# GPS_MPU_Schematic.net
KiCad netlist of a schematic drawn in EasyEDA
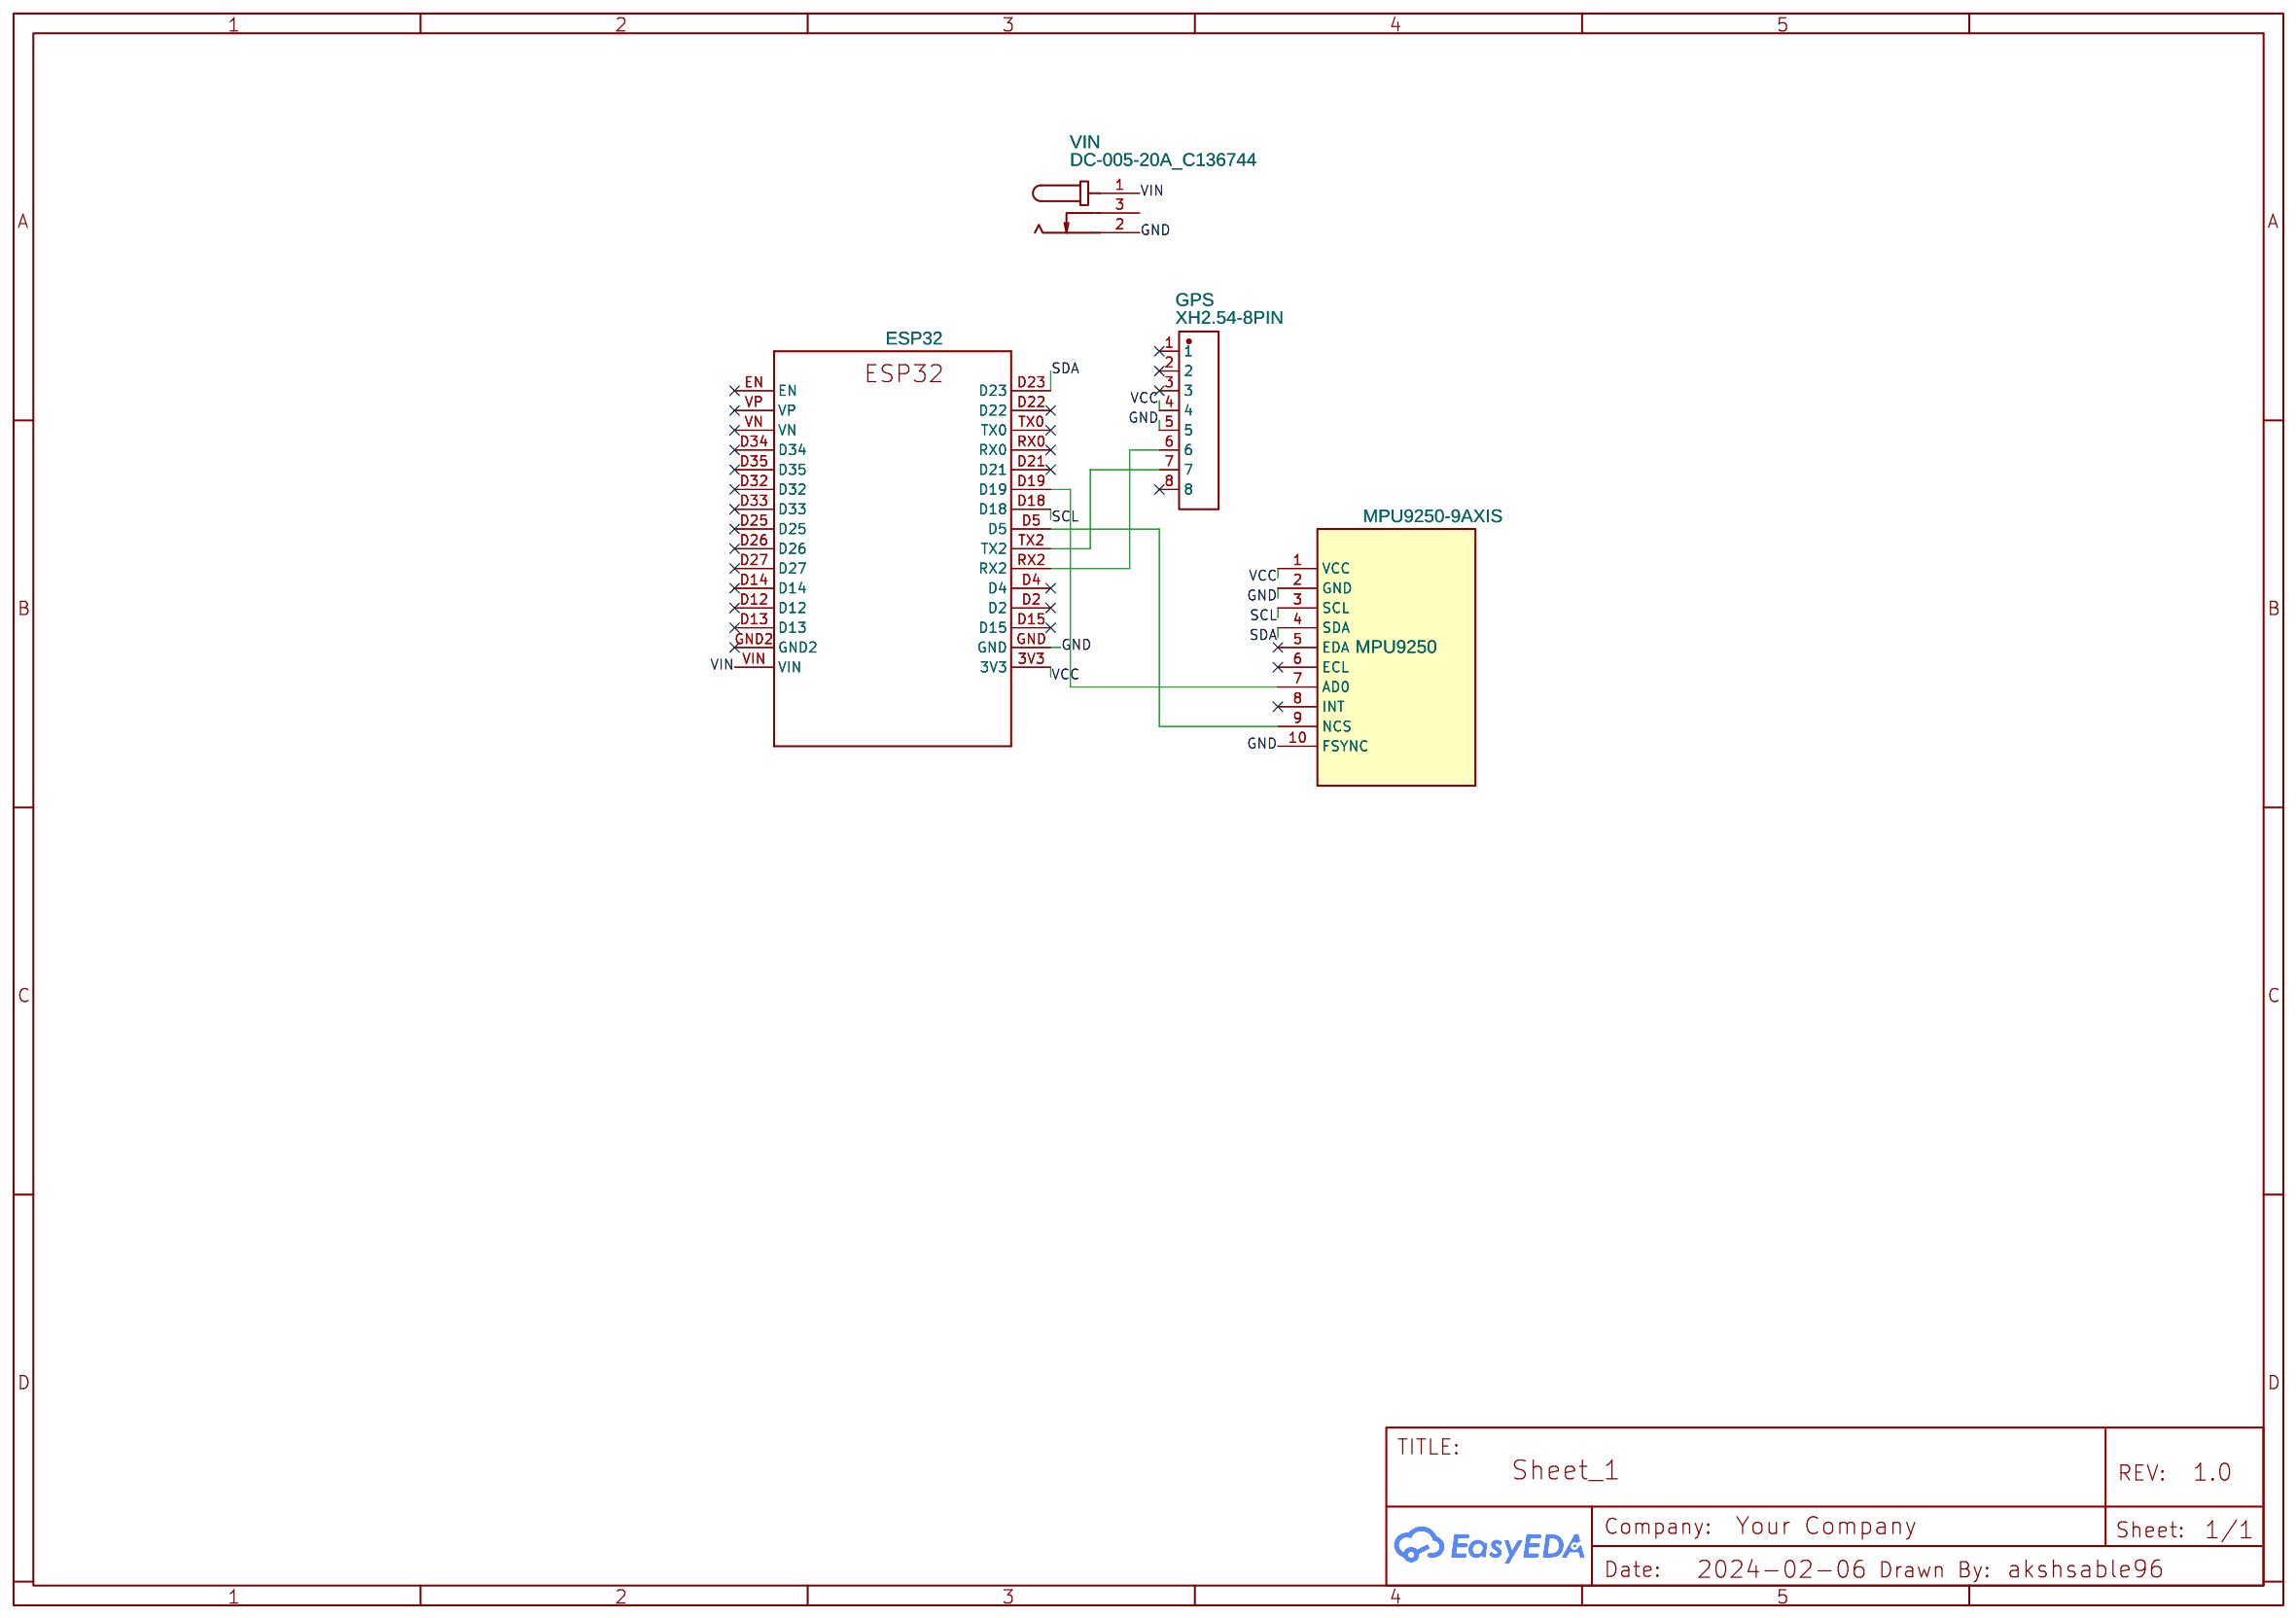
[diagram p0: schematic sheet]

(export (version "E")
  (design (tool "Eeschema 10.0.6"))
  (components
    (comp (ref "2") (value "ESP32") (libsource (lib "") (part "ESP32-DEVKIT-V1-30PIN")))
    (comp (ref "GPS") (value "XH2.54-8PIN") (libsource (lib "") (part "XH2.54-8PIN")))
    (comp (ref "MPU9250") (value "MPU9250-9AXIS") (libsource (lib "") (part "MPU9250-9AXIS")))
    (comp (ref "VIN")
      (value "DC-005-20A_C136744")
      (fields (field (name "Manufacturer Part") "DC-005-20A") (field (name "Manufacturer") "韩国韩荣"))
      (libsource (lib "") (part "DC-005-20A_C136744"))
    )
  )
  (nets
    (net (code "1") (name "/GND") (class "Default")
      (node (ref "2") (pin "GND") (pinfunction "GND_GND") (pintype "unspecified"))
      (node (ref "GPS") (pin "5") (pinfunction "5_5") (pintype "unspecified"))
      (node (ref "MPU9250") (pin "10") (pinfunction "FSYNC_10") (pintype "unspecified"))
      (node (ref "MPU9250") (pin "2") (pinfunction "GND_2") (pintype "unspecified"))
      (node (ref "VIN") (pin "2") (pinfunction "2_2") (pintype "unspecified"))
    )
    (net (code "2") (name "/SCL") (class "Default")
      (node (ref "2") (pin "D18") (pinfunction "D18_D18") (pintype "unspecified"))
      (node (ref "MPU9250") (pin "3") (pinfunction "SCL_3") (pintype "unspecified"))
    )
    (net (code "3") (name "/SDA") (class "Default")
      (node (ref "2") (pin "D23") (pinfunction "D23_D23") (pintype "unspecified"))
      (node (ref "MPU9250") (pin "4") (pinfunction "SDA_4") (pintype "unspecified"))
    )
    (net (code "4") (name "/VCC") (class "Default")
      (node (ref "2") (pin "3V3") (pinfunction "3V3_3V3") (pintype "unspecified"))
      (node (ref "GPS") (pin "4") (pinfunction "4_4") (pintype "unspecified"))
      (node (ref "MPU9250") (pin "1") (pinfunction "VCC_1") (pintype "unspecified"))
    )
    (net (code "5") (name "/VIN") (class "Default")
      (node (ref "2") (pin "VIN") (pinfunction "VIN_VIN") (pintype "unspecified"))
      (node (ref "VIN") (pin "1") (pinfunction "1_1") (pintype "unspecified"))
    )
    (net (code "6") (name "Net-(2-PadRX2)") (class "Default")
      (node (ref "2") (pin "RX2") (pinfunction "RX2_RX2") (pintype "unspecified"))
      (node (ref "GPS") (pin "6") (pinfunction "6_6") (pintype "unspecified"))
    )
    (net (code "7") (name "Net-(2-PadTX2)") (class "Default")
      (node (ref "2") (pin "TX2") (pinfunction "TX2_TX2") (pintype "unspecified"))
      (node (ref "GPS") (pin "7") (pinfunction "7_7") (pintype "unspecified"))
    )
    (net (code "8") (name "Net-(MPU9250-AD0)") (class "Default")
      (node (ref "2") (pin "D19") (pinfunction "D19_D19") (pintype "unspecified"))
      (node (ref "MPU9250") (pin "7") (pinfunction "AD0_7") (pintype "unspecified"))
    )
    (net (code "9") (name "Net-(MPU9250-NCS)") (class "Default")
      (node (ref "2") (pin "D5") (pinfunction "D5_D5") (pintype "unspecified"))
      (node (ref "MPU9250") (pin "9") (pinfunction "NCS_9") (pintype "unspecified"))
    )
    (net (code "10") (name "unconnected-(2-PadD2)") (class "Default")
      (node (ref "2") (pin "D2") (pinfunction "D2_D2") (pintype "unspecified+no_connect"))
    )
    (net (code "11") (name "unconnected-(2-PadD4)") (class "Default")
      (node (ref "2") (pin "D4") (pinfunction "D4_D4") (pintype "unspecified+no_connect"))
    )
    (net (code "12") (name "unconnected-(2-PadD12)") (class "Default")
      (node (ref "2") (pin "D12") (pinfunction "D12_D12") (pintype "unspecified+no_connect"))
    )
    (net (code "13") (name "unconnected-(2-PadD13)") (class "Default")
      (node (ref "2") (pin "D13") (pinfunction "D13_D13") (pintype "unspecified+no_connect"))
    )
    (net (code "14") (name "unconnected-(2-PadD14)") (class "Default")
      (node (ref "2") (pin "D14") (pinfunction "D14_D14") (pintype "unspecified+no_connect"))
    )
    (net (code "15") (name "unconnected-(2-PadD15)") (class "Default")
      (node (ref "2") (pin "D15") (pinfunction "D15_D15") (pintype "unspecified+no_connect"))
    )
    (net (code "16") (name "unconnected-(2-PadD21)") (class "Default")
      (node (ref "2") (pin "D21") (pinfunction "D21_D21") (pintype "unspecified+no_connect"))
    )
    (net (code "17") (name "unconnected-(2-PadD22)") (class "Default")
      (node (ref "2") (pin "D22") (pinfunction "D22_D22") (pintype "unspecified+no_connect"))
    )
    (net (code "18") (name "unconnected-(2-PadD25)") (class "Default")
      (node (ref "2") (pin "D25") (pinfunction "D25_D25") (pintype "unspecified+no_connect"))
    )
    (net (code "19") (name "unconnected-(2-PadD26)") (class "Default")
      (node (ref "2") (pin "D26") (pinfunction "D26_D26") (pintype "unspecified+no_connect"))
    )
    (net (code "20") (name "unconnected-(2-PadD27)") (class "Default")
      (node (ref "2") (pin "D27") (pinfunction "D27_D27") (pintype "unspecified+no_connect"))
    )
    (net (code "21") (name "unconnected-(2-PadD32)") (class "Default")
      (node (ref "2") (pin "D32") (pinfunction "D32_D32") (pintype "unspecified+no_connect"))
    )
    (net (code "22") (name "unconnected-(2-PadD33)") (class "Default")
      (node (ref "2") (pin "D33") (pinfunction "D33_D33") (pintype "unspecified+no_connect"))
    )
    (net (code "23") (name "unconnected-(2-PadD34)") (class "Default")
      (node (ref "2") (pin "D34") (pinfunction "D34_D34") (pintype "unspecified+no_connect"))
    )
    (net (code "24") (name "unconnected-(2-PadD35)") (class "Default")
      (node (ref "2") (pin "D35") (pinfunction "D35_D35") (pintype "unspecified+no_connect"))
    )
    (net (code "25") (name "unconnected-(2-PadEN)") (class "Default")
      (node (ref "2") (pin "EN") (pinfunction "EN_EN") (pintype "unspecified+no_connect"))
    )
    (net (code "26") (name "unconnected-(2-PadGND2)") (class "Default")
      (node (ref "2") (pin "GND2") (pinfunction "GND2_GND2") (pintype "unspecified+no_connect"))
    )
    (net (code "27") (name "unconnected-(2-PadRX0)") (class "Default")
      (node (ref "2") (pin "RX0") (pinfunction "RX0_RX0") (pintype "unspecified+no_connect"))
    )
    (net (code "28") (name "unconnected-(2-PadTX0)") (class "Default")
      (node (ref "2") (pin "TX0") (pinfunction "TX0_TX0") (pintype "unspecified+no_connect"))
    )
    (net (code "29") (name "unconnected-(2-PadVN)") (class "Default")
      (node (ref "2") (pin "VN") (pinfunction "VN_VN") (pintype "unspecified+no_connect"))
    )
    (net (code "30") (name "unconnected-(2-PadVP)") (class "Default")
      (node (ref "2") (pin "VP") (pinfunction "VP_VP") (pintype "unspecified+no_connect"))
    )
    (net (code "31") (name "unconnected-(GPS-Pad1)") (class "Default")
      (node (ref "GPS") (pin "1") (pinfunction "1_1") (pintype "unspecified+no_connect"))
    )
    (net (code "32") (name "unconnected-(GPS-Pad2)") (class "Default")
      (node (ref "GPS") (pin "2") (pinfunction "2_2") (pintype "unspecified+no_connect"))
    )
    (net (code "33") (name "unconnected-(GPS-Pad3)") (class "Default")
      (node (ref "GPS") (pin "3") (pinfunction "3_3") (pintype "unspecified+no_connect"))
    )
    (net (code "34") (name "unconnected-(GPS-Pad8)") (class "Default")
      (node (ref "GPS") (pin "8") (pinfunction "8_8") (pintype "unspecified+no_connect"))
    )
    (net (code "35") (name "unconnected-(MPU9250-ECL-Pad6)") (class "Default")
      (node (ref "MPU9250") (pin "6") (pinfunction "ECL_6") (pintype "unspecified+no_connect"))
    )
    (net (code "36") (name "unconnected-(MPU9250-EDA-Pad5)") (class "Default")
      (node (ref "MPU9250") (pin "5") (pinfunction "EDA_5") (pintype "unspecified+no_connect"))
    )
    (net (code "37") (name "unconnected-(MPU9250-INT-Pad8)") (class "Default")
      (node (ref "MPU9250") (pin "8") (pinfunction "INT_8") (pintype "unspecified+no_connect"))
    )
    (net (code "38") (name "unconnected-(VIN-Pad3)") (class "Default")
      (node (ref "VIN") (pin "3") (pinfunction "3_3") (pintype "unspecified"))
    )
  )
)
